# Smart-Watch-Front.net
KiCad netlist of a schematic drawn in Altium Designer
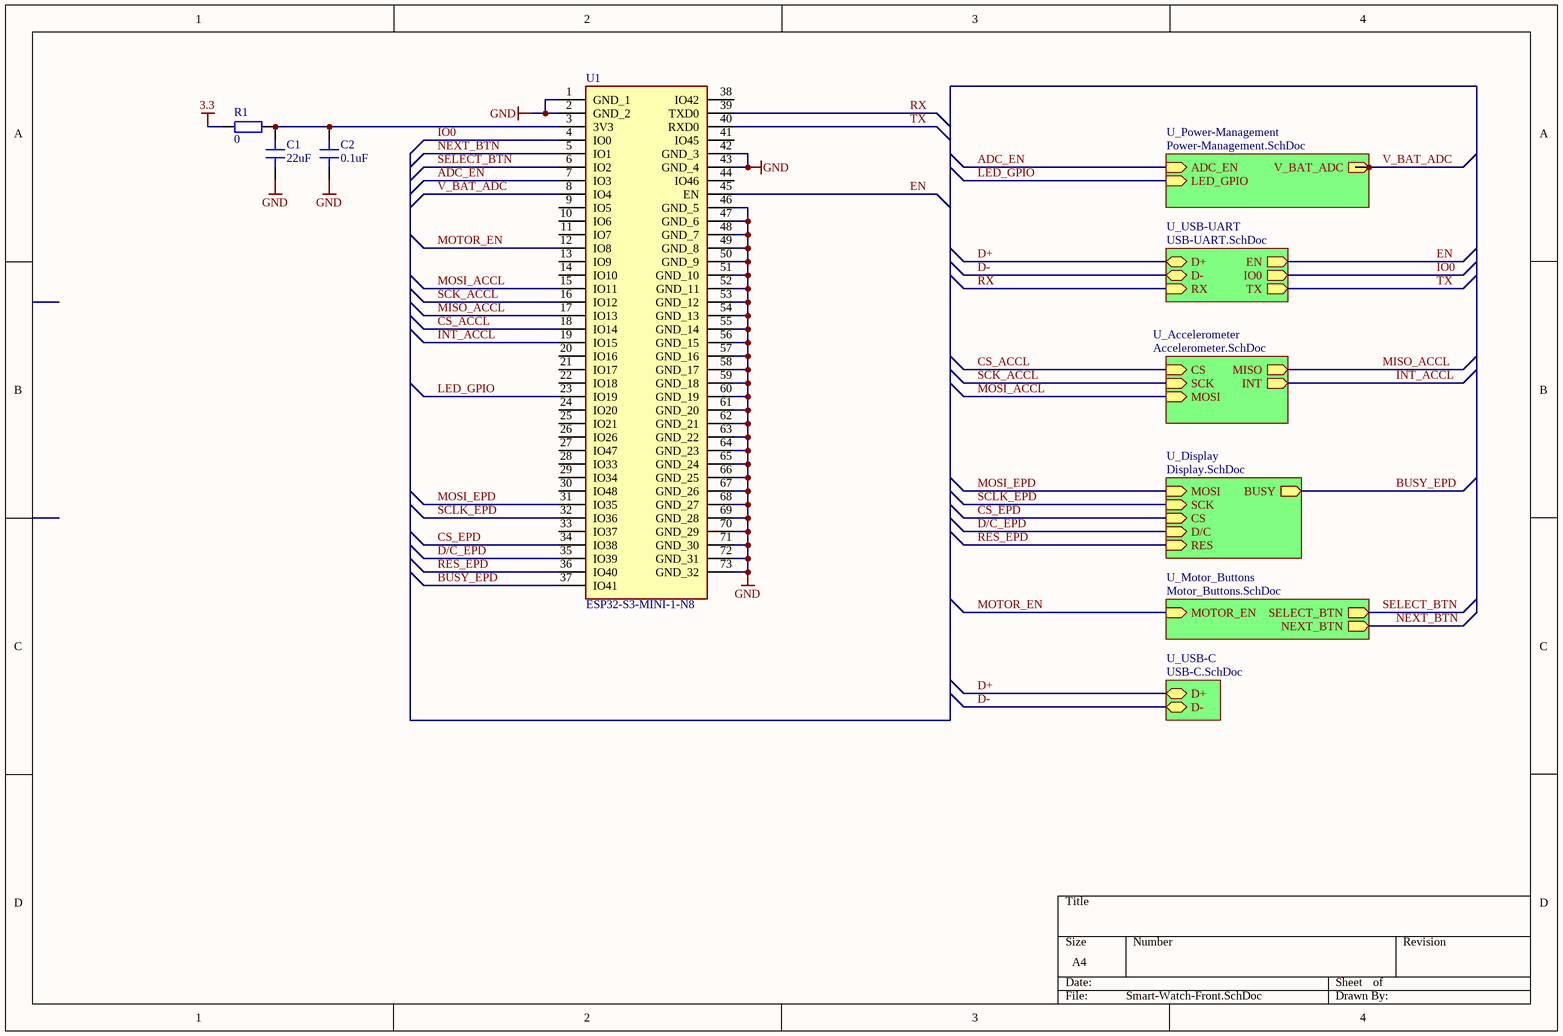
[diagram p0: Smart-Watch-Front.SchDoc]

(export (version "E")
  (design (tool "Eeschema 10.0.6"))
  (components
    (comp (ref "C1") (value "22uF") (footprint "0603_CAP") (libsource (lib "passive_components") (part "C")))
    (comp (ref "C2") (value "0.1uF") (footprint "0603_CAP") (libsource (lib "passive_components") (part "C")))
    (comp (ref "R1") (value "0") (footprint "0603") (libsource (lib "passive_components") (part "R")))
    (comp (ref "U1")
      (value "ESP32-S3-MINI-1-N8")
      (footprint "ESP32S3MINI1N8")
      (description "Integrated Circuit")
      (fields (field (name "MOUSER PART NUMBER") "356-ESP32-S3-MINI1N8"))
      (libsource (lib "Display_Connector") (part "ESP32-S3-MINI-1-N8"))
    )
  )
  (nets
    (net (code "1") (name "/ADC_EN") (class "Default")
      (node (ref "U1") (pin "7") (pinfunction "IO3_7") (pintype "passive"))
    )
    (net (code "2") (name "/BUSY_EPD") (class "Default")
      (node (ref "U1") (pin "37") (pinfunction "IO41_37") (pintype "passive"))
    )
    (net (code "3") (name "/CS_ACCL") (class "Default")
      (node (ref "U1") (pin "18") (pinfunction "IO14_18") (pintype "passive"))
    )
    (net (code "4") (name "/CS_EPD") (class "Default")
      (node (ref "U1") (pin "34") (pinfunction "IO38_34") (pintype "passive"))
    )
    (net (code "7") (name "/D{slash}C_EPD") (class "Default")
      (node (ref "U1") (pin "35") (pinfunction "IO39_35") (pintype "passive"))
    )
    (net (code "8") (name "/EN") (class "Default")
      (node (ref "U1") (pin "45") (pinfunction "EN_45") (pintype "passive"))
    )
    (net (code "9") (name "/INT_ACCL") (class "Default")
      (node (ref "U1") (pin "19") (pinfunction "IO15_19") (pintype "passive"))
    )
    (net (code "10") (name "/IO0") (class "Default")
      (node (ref "U1") (pin "4") (pinfunction "IO0_4") (pintype "passive"))
    )
    (net (code "11") (name "/LED_GPIO") (class "Default")
      (node (ref "U1") (pin "23") (pinfunction "IO19_23") (pintype "passive"))
    )
    (net (code "12") (name "/MISO_ACCL") (class "Default")
      (node (ref "U1") (pin "17") (pinfunction "IO13_17") (pintype "passive"))
    )
    (net (code "13") (name "/MOSI_ACCL") (class "Default")
      (node (ref "U1") (pin "15") (pinfunction "IO11_15") (pintype "passive"))
    )
    (net (code "14") (name "/MOSI_EPD") (class "Default")
      (node (ref "U1") (pin "31") (pinfunction "IO35_31") (pintype "passive"))
    )
    (net (code "15") (name "/MOTOR_EN") (class "Default")
      (node (ref "U1") (pin "12") (pinfunction "IO8_12") (pintype "passive"))
    )
    (net (code "16") (name "/NEXT_BTN") (class "Default")
      (node (ref "U1") (pin "5") (pinfunction "IO1_5") (pintype "passive"))
    )
    (net (code "17") (name "/RES_EPD") (class "Default")
      (node (ref "U1") (pin "36") (pinfunction "IO40_36") (pintype "passive"))
    )
    (net (code "18") (name "/RX") (class "Default")
      (node (ref "U1") (pin "39") (pinfunction "TXD0_39") (pintype "passive"))
    )
    (net (code "19") (name "/SCK_ACCL") (class "Default")
      (node (ref "U1") (pin "16") (pinfunction "IO12_16") (pintype "passive"))
    )
    (net (code "20") (name "/SCLK_EPD") (class "Default")
      (node (ref "U1") (pin "32") (pinfunction "IO36_32") (pintype "passive"))
    )
    (net (code "21") (name "/SELECT_BTN") (class "Default")
      (node (ref "U1") (pin "6") (pinfunction "IO2_6") (pintype "passive"))
    )
    (net (code "22") (name "/TX") (class "Default")
      (node (ref "U1") (pin "40") (pinfunction "RXD0_40") (pintype "passive"))
    )
    (net (code "23") (name "/V_BAT_ADC") (class "Default")
      (node (ref "U1") (pin "8") (pinfunction "IO4_8") (pintype "passive"))
    )
    (net (code "24") (name "3.3") (class "Default")
      (node (ref "R1") (pin "1") (pinfunction "25_1") (pintype "passive"))
    )
    (net (code "25") (name "GND") (class "Default")
      (node (ref "C1") (pin "1") (pinfunction "1_1") (pintype "passive"))
      (node (ref "C2") (pin "1") (pinfunction "1_1") (pintype "passive"))
      (node (ref "U1") (pin "1") (pinfunction "GND_1_1") (pintype "passive"))
      (node (ref "U1") (pin "2") (pinfunction "GND_2_2") (pintype "passive"))
      (node (ref "U1") (pin "42") (pinfunction "GND_3_42") (pintype "passive"))
      (node (ref "U1") (pin "43") (pinfunction "GND_4_43") (pintype "passive"))
      (node (ref "U1") (pin "46") (pinfunction "GND_5_46") (pintype "passive"))
      (node (ref "U1") (pin "47") (pinfunction "GND_6_47") (pintype "passive"))
      (node (ref "U1") (pin "48") (pinfunction "GND_7_48") (pintype "passive"))
      (node (ref "U1") (pin "49") (pinfunction "GND_8_49") (pintype "passive"))
      (node (ref "U1") (pin "50") (pinfunction "GND_9_50") (pintype "passive"))
      (node (ref "U1") (pin "51") (pinfunction "GND_10_51") (pintype "passive"))
      (node (ref "U1") (pin "52") (pinfunction "GND_11_52") (pintype "passive"))
      (node (ref "U1") (pin "53") (pinfunction "GND_12_53") (pintype "passive"))
      (node (ref "U1") (pin "54") (pinfunction "GND_13_54") (pintype "passive"))
      (node (ref "U1") (pin "55") (pinfunction "GND_14_55") (pintype "passive"))
      (node (ref "U1") (pin "56") (pinfunction "GND_15_56") (pintype "passive"))
      (node (ref "U1") (pin "57") (pinfunction "GND_16_57") (pintype "passive"))
      (node (ref "U1") (pin "58") (pinfunction "GND_17_58") (pintype "passive"))
      (node (ref "U1") (pin "59") (pinfunction "GND_18_59") (pintype "passive"))
      (node (ref "U1") (pin "60") (pinfunction "GND_19_60") (pintype "passive"))
      (node (ref "U1") (pin "61") (pinfunction "GND_20_61") (pintype "passive"))
      (node (ref "U1") (pin "62") (pinfunction "GND_21_62") (pintype "passive"))
      (node (ref "U1") (pin "63") (pinfunction "GND_22_63") (pintype "passive"))
      (node (ref "U1") (pin "64") (pinfunction "GND_23_64") (pintype "passive"))
      (node (ref "U1") (pin "65") (pinfunction "GND_24_65") (pintype "passive"))
      (node (ref "U1") (pin "66") (pinfunction "GND_25_66") (pintype "passive"))
      (node (ref "U1") (pin "67") (pinfunction "GND_26_67") (pintype "passive"))
      (node (ref "U1") (pin "68") (pinfunction "GND_27_68") (pintype "passive"))
      (node (ref "U1") (pin "69") (pinfunction "GND_28_69") (pintype "passive"))
      (node (ref "U1") (pin "70") (pinfunction "GND_29_70") (pintype "passive"))
      (node (ref "U1") (pin "71") (pinfunction "GND_30_71") (pintype "passive"))
      (node (ref "U1") (pin "72") (pinfunction "GND_31_72") (pintype "passive"))
      (node (ref "U1") (pin "73") (pinfunction "GND_32_73") (pintype "passive"))
    )
    (net (code "26") (name "Net-(C1-28)") (class "Default")
      (node (ref "C1") (pin "2") (pinfunction "28_2") (pintype "passive"))
      (node (ref "C2") (pin "2") (pinfunction "28_2") (pintype "passive"))
      (node (ref "R1") (pin "2") (pinfunction "26_2") (pintype "passive"))
      (node (ref "U1") (pin "3") (pinfunction "3V3_3") (pintype "passive"))
    )
    (net (code "27") (name "unconnected-(U1-IO5-Pad9)") (class "Default")
      (node (ref "U1") (pin "9") (pinfunction "IO5_9") (pintype "passive"))
    )
    (net (code "28") (name "unconnected-(U1-IO6-Pad10)") (class "Default")
      (node (ref "U1") (pin "10") (pinfunction "IO6_10") (pintype "passive"))
    )
    (net (code "29") (name "unconnected-(U1-IO7-Pad11)") (class "Default")
      (node (ref "U1") (pin "11") (pinfunction "IO7_11") (pintype "passive"))
    )
    (net (code "30") (name "unconnected-(U1-IO9-Pad13)") (class "Default")
      (node (ref "U1") (pin "13") (pinfunction "IO9_13") (pintype "passive"))
    )
    (net (code "31") (name "unconnected-(U1-IO10-Pad14)") (class "Default")
      (node (ref "U1") (pin "14") (pinfunction "IO10_14") (pintype "passive"))
    )
    (net (code "32") (name "unconnected-(U1-IO16-Pad20)") (class "Default")
      (node (ref "U1") (pin "20") (pinfunction "IO16_20") (pintype "passive"))
    )
    (net (code "33") (name "unconnected-(U1-IO17-Pad21)") (class "Default")
      (node (ref "U1") (pin "21") (pinfunction "IO17_21") (pintype "passive"))
    )
    (net (code "34") (name "unconnected-(U1-IO18-Pad22)") (class "Default")
      (node (ref "U1") (pin "22") (pinfunction "IO18_22") (pintype "passive"))
    )
    (net (code "35") (name "unconnected-(U1-IO20-Pad24)") (class "Default")
      (node (ref "U1") (pin "24") (pinfunction "IO20_24") (pintype "passive"))
    )
    (net (code "36") (name "unconnected-(U1-IO21-Pad25)") (class "Default")
      (node (ref "U1") (pin "25") (pinfunction "IO21_25") (pintype "passive"))
    )
    (net (code "37") (name "unconnected-(U1-IO26-Pad26)") (class "Default")
      (node (ref "U1") (pin "26") (pinfunction "IO26_26") (pintype "passive"))
    )
    (net (code "38") (name "unconnected-(U1-IO33-Pad28)") (class "Default")
      (node (ref "U1") (pin "28") (pinfunction "IO33_28") (pintype "passive"))
    )
    (net (code "39") (name "unconnected-(U1-IO34-Pad29)") (class "Default")
      (node (ref "U1") (pin "29") (pinfunction "IO34_29") (pintype "passive"))
    )
    (net (code "40") (name "unconnected-(U1-IO37-Pad33)") (class "Default")
      (node (ref "U1") (pin "33") (pinfunction "IO37_33") (pintype "passive"))
    )
    (net (code "41") (name "unconnected-(U1-IO42-Pad38)") (class "Default")
      (node (ref "U1") (pin "38") (pinfunction "IO42_38") (pintype "passive"))
    )
    (net (code "42") (name "unconnected-(U1-IO45-Pad41)") (class "Default")
      (node (ref "U1") (pin "41") (pinfunction "IO45_41") (pintype "passive"))
    )
    (net (code "43") (name "unconnected-(U1-IO46-Pad44)") (class "Default")
      (node (ref "U1") (pin "44") (pinfunction "IO46_44") (pintype "passive"))
    )
    (net (code "44") (name "unconnected-(U1-IO47-Pad27)") (class "Default")
      (node (ref "U1") (pin "27") (pinfunction "IO47_27") (pintype "passive"))
    )
    (net (code "45") (name "unconnected-(U1-IO48-Pad30)") (class "Default")
      (node (ref "U1") (pin "30") (pinfunction "IO48_30") (pintype "passive"))
    )
  )
)
